# DAC900E.net
KiCad netlist of a schematic drawn in EAGLE
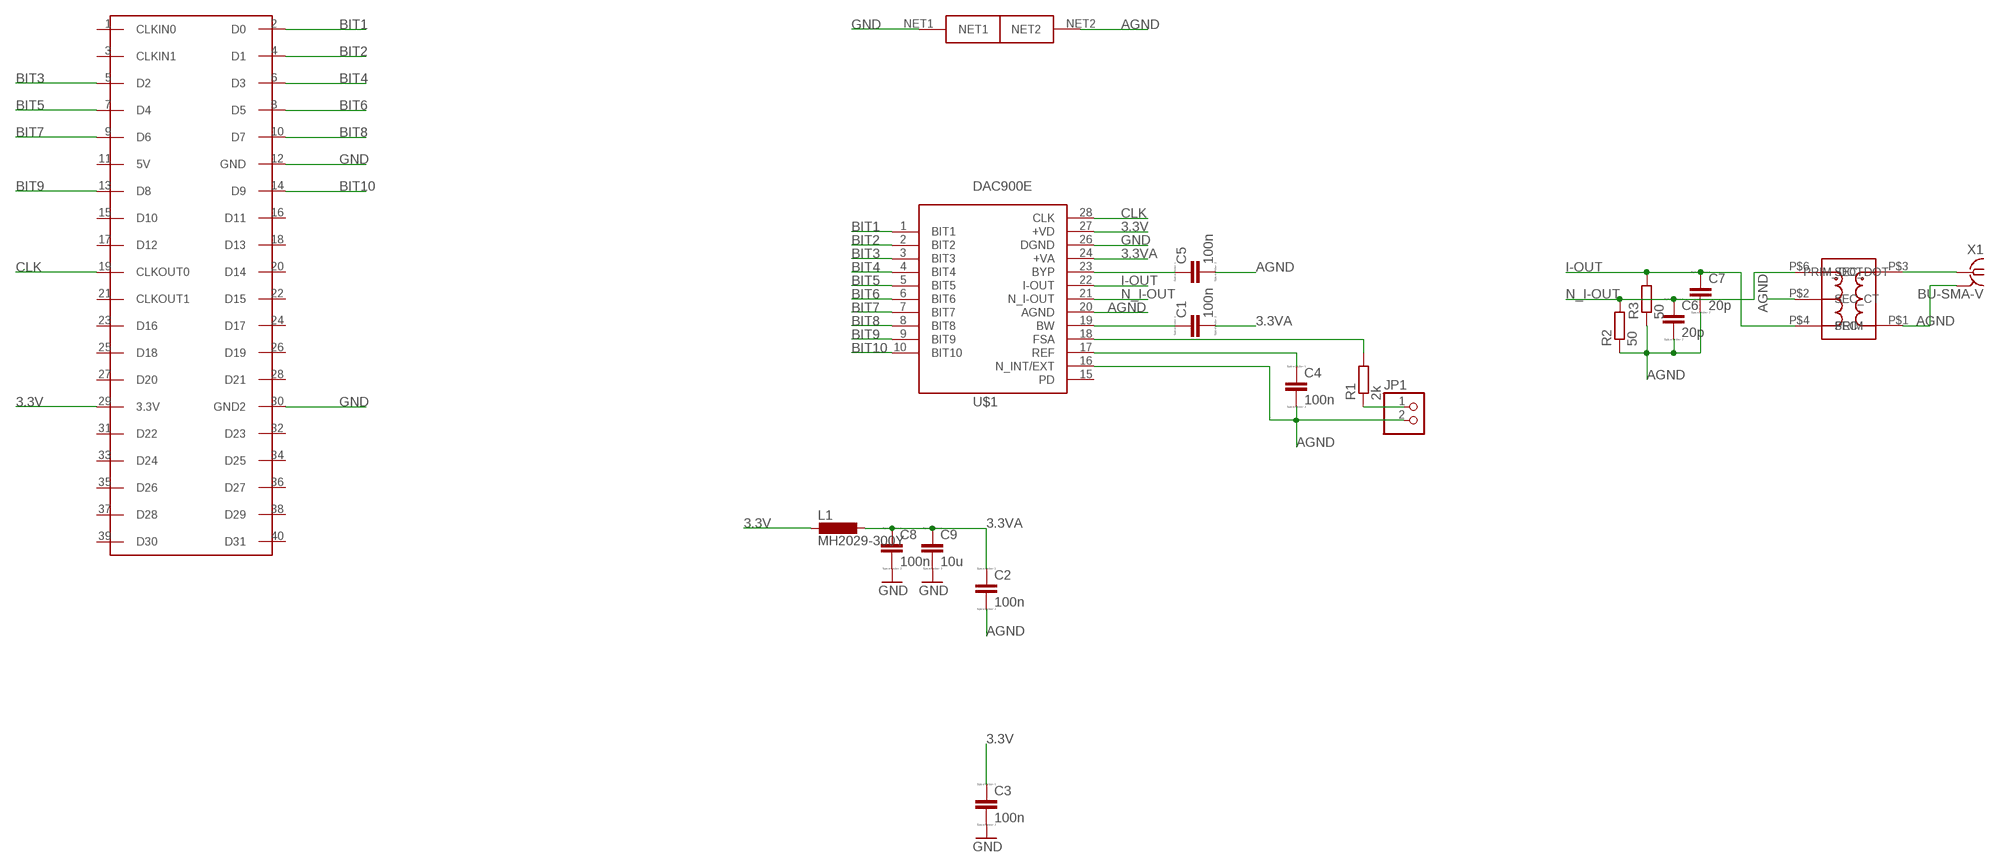
[diagram p0: schematic, sheet 1]

(export (version "E")
  (design (tool "Eeschema 10.0.6"))
  (components
    (comp (ref "C1")
      (value "100n")
      (footprint "eagle-import:C0805")
      (libsource (lib "eagle-import") (part "C_SMD"))
    )
    (comp (ref "C2")
      (value "100n")
      (footprint "eagle-import:C0805")
      (libsource (lib "eagle-import") (part "C_SMD"))
    )
    (comp (ref "C3")
      (value "100n")
      (footprint "eagle-import:C0805")
      (libsource (lib "eagle-import") (part "C_SMD"))
    )
    (comp (ref "C4")
      (value "100n")
      (footprint "eagle-import:C0805")
      (libsource (lib "eagle-import") (part "C_SMD"))
    )
    (comp (ref "C5")
      (value "100n")
      (footprint "eagle-import:C0805")
      (libsource (lib "eagle-import") (part "C_SMD"))
    )
    (comp (ref "C6")
      (value "20p")
      (footprint "eagle-import:C0805")
      (libsource (lib "eagle-import") (part "C_SMD"))
    )
    (comp (ref "C7")
      (value "20p")
      (footprint "eagle-import:C0805")
      (libsource (lib "eagle-import") (part "C_SMD"))
    )
    (comp (ref "C8")
      (value "100n")
      (footprint "eagle-import:C0805")
      (libsource (lib "eagle-import") (part "C_SMD"))
    )
    (comp (ref "C9")
      (value "10u")
      (footprint "eagle-import:C0805")
      (libsource (lib "eagle-import") (part "C_SMD"))
    )
    (comp (ref "JP1")
      (value "PINHD-1X2")
      (footprint "eagle-import:1X02")
      (libsource (lib "eagle-import") (part "PINHD-1X2"))
    )
    (comp (ref "L1")
      (value "MH2029-300Y")
      (footprint "eagle-import:R0805")
      (libsource (lib "eagle-import") (part "L_0805"))
    )
    (comp (ref "R1")
      (value "2k")
      (footprint "eagle-import:R0805")
      (libsource (lib "eagle-import") (part "R-EU_R0805"))
    )
    (comp (ref "R2")
      (value "50")
      (footprint "eagle-import:R0805")
      (libsource (lib "eagle-import") (part "R-EU_R0805"))
    )
    (comp (ref "R3")
      (value "50")
      (footprint "eagle-import:R0805")
      (libsource (lib "eagle-import") (part "R-EU_R0805"))
    )
    (comp (ref "U$1")
      (value "DAC900E")
      (footprint "eagle-import:TSSOP28")
      (libsource (lib "eagle-import") (part "DAC900E"))
    )
    (comp (ref "U$2")
      (value "NET_TIE")
      (footprint "eagle-import:NET-TIE")
      (libsource (lib "eagle-import") (part "NET_TIE"))
    )
    (comp (ref "U$3")
      (value "FPGA_GPIO_DE0")
      (footprint "eagle-import:2X20")
      (libsource (lib "eagle-import") (part "FPGA_GPIO_DE0"))
    )
    (comp (ref "U$4")
      (value "ADT1-1WT")
      (footprint "eagle-import:CD542")
      (libsource (lib "eagle-import") (part "ADT1-1WT"))
    )
    (comp (ref "X1")
      (value "BU-SMA-V")
      (footprint "eagle-import:BU-SMA-V")
      (libsource (lib "eagle-import") (part "BU-SMA-V"))
    )
  )
  (nets
    (net (code "1") (name "/3.3V") (class "Default")
      (node (ref "C3") (pin "1") (pinfunction "1_1") (pintype "passive"))
      (node (ref "L1") (pin "2") (pinfunction "2_2") (pintype "passive"))
      (node (ref "U$1") (pin "27") (pinfunction "+VD_27") (pintype "bidirectional"))
      (node (ref "U$3") (pin "29") (pinfunction "3.3V_29") (pintype "bidirectional"))
    )
    (net (code "2") (name "/3.3VA") (class "Default")
      (node (ref "C1") (pin "2") (pinfunction "2_2") (pintype "passive"))
      (node (ref "C2") (pin "1") (pinfunction "1_1") (pintype "passive"))
      (node (ref "C8") (pin "1") (pinfunction "1_1") (pintype "passive"))
      (node (ref "C9") (pin "1") (pinfunction "1_1") (pintype "passive"))
      (node (ref "L1") (pin "1") (pinfunction "1_1") (pintype "passive"))
      (node (ref "U$1") (pin "24") (pinfunction "+VA_24") (pintype "bidirectional"))
    )
    (net (code "3") (name "/AGND") (class "Default")
      (node (ref "C2") (pin "2") (pinfunction "2_2") (pintype "passive"))
      (node (ref "C4") (pin "2") (pinfunction "2_2") (pintype "passive"))
      (node (ref "C5") (pin "2") (pinfunction "2_2") (pintype "passive"))
      (node (ref "C6") (pin "2") (pinfunction "2_2") (pintype "passive"))
      (node (ref "C7") (pin "2") (pinfunction "2_2") (pintype "passive"))
      (node (ref "JP1") (pin "2") (pinfunction "2_2") (pintype "passive"))
      (node (ref "R2") (pin "1") (pinfunction "1_1") (pintype "passive"))
      (node (ref "R3") (pin "1") (pinfunction "1_1") (pintype "passive"))
      (node (ref "U$1") (pin "16") (pinfunction "N_INT/EXT_16") (pintype "bidirectional"))
      (node (ref "U$1") (pin "20") (pinfunction "AGND_20") (pintype "bidirectional"))
      (node (ref "U$2") (pin "NET2") (pinfunction "NET2_NET2") (pintype "bidirectional"))
      (node (ref "U$4") (pin "P$1") (pinfunction "PRIM_P$1") (pintype "bidirectional"))
      (node (ref "U$4") (pin "P$2") (pinfunction "SEC_CT_P$2") (pintype "bidirectional"))
      (node (ref "X1") (pin "2") (pinfunction "2_2") (pintype "passive"))
      (node (ref "X1") (pin "3") (pinfunction "2_3") (pintype "passive"))
      (node (ref "X1") (pin "4") (pinfunction "2_4") (pintype "passive"))
      (node (ref "X1") (pin "5") (pinfunction "2_5") (pintype "passive"))
    )
    (net (code "4") (name "/BIT1") (class "Default")
      (node (ref "U$1") (pin "1") (pinfunction "BIT1_1") (pintype "bidirectional"))
      (node (ref "U$3") (pin "2") (pinfunction "D0_2") (pintype "bidirectional"))
    )
    (net (code "5") (name "/BIT2") (class "Default")
      (node (ref "U$1") (pin "2") (pinfunction "BIT2_2") (pintype "bidirectional"))
      (node (ref "U$3") (pin "4") (pinfunction "D1_4") (pintype "bidirectional"))
    )
    (net (code "6") (name "/BIT3") (class "Default")
      (node (ref "U$1") (pin "3") (pinfunction "BIT3_3") (pintype "bidirectional"))
      (node (ref "U$3") (pin "5") (pinfunction "D2_5") (pintype "bidirectional"))
    )
    (net (code "7") (name "/BIT4") (class "Default")
      (node (ref "U$1") (pin "4") (pinfunction "BIT4_4") (pintype "bidirectional"))
      (node (ref "U$3") (pin "6") (pinfunction "D3_6") (pintype "bidirectional"))
    )
    (net (code "8") (name "/BIT5") (class "Default")
      (node (ref "U$1") (pin "5") (pinfunction "BIT5_5") (pintype "bidirectional"))
      (node (ref "U$3") (pin "7") (pinfunction "D4_7") (pintype "bidirectional"))
    )
    (net (code "9") (name "/BIT6") (class "Default")
      (node (ref "U$1") (pin "6") (pinfunction "BIT6_6") (pintype "bidirectional"))
      (node (ref "U$3") (pin "8") (pinfunction "D5_8") (pintype "bidirectional"))
    )
    (net (code "10") (name "/BIT7") (class "Default")
      (node (ref "U$1") (pin "7") (pinfunction "BIT7_7") (pintype "bidirectional"))
      (node (ref "U$3") (pin "9") (pinfunction "D6_9") (pintype "bidirectional"))
    )
    (net (code "11") (name "/BIT8") (class "Default")
      (node (ref "U$1") (pin "8") (pinfunction "BIT8_8") (pintype "bidirectional"))
      (node (ref "U$3") (pin "10") (pinfunction "D7_10") (pintype "bidirectional"))
    )
    (net (code "12") (name "/BIT9") (class "Default")
      (node (ref "U$1") (pin "9") (pinfunction "BIT9_9") (pintype "bidirectional"))
      (node (ref "U$3") (pin "13") (pinfunction "D8_13") (pintype "bidirectional"))
    )
    (net (code "13") (name "/BIT10") (class "Default")
      (node (ref "U$1") (pin "10") (pinfunction "BIT10_10") (pintype "bidirectional"))
      (node (ref "U$3") (pin "14") (pinfunction "D9_14") (pintype "bidirectional"))
    )
    (net (code "14") (name "/CLK") (class "Default")
      (node (ref "U$1") (pin "28") (pinfunction "CLK_28") (pintype "bidirectional"))
      (node (ref "U$3") (pin "19") (pinfunction "CLKOUT0_19") (pintype "bidirectional"))
    )
    (net (code "15") (name "/I-OUT") (class "Default")
      (node (ref "C7") (pin "1") (pinfunction "1_1") (pintype "passive"))
      (node (ref "R3") (pin "2") (pinfunction "2_2") (pintype "passive"))
      (node (ref "U$1") (pin "22") (pinfunction "I-OUT_22") (pintype "bidirectional"))
      (node (ref "U$4") (pin "P$4") (pinfunction "SEC_P$4") (pintype "bidirectional"))
    )
    (net (code "16") (name "/N_I-OUT") (class "Default")
      (node (ref "C6") (pin "1") (pinfunction "1_1") (pintype "passive"))
      (node (ref "R2") (pin "2") (pinfunction "2_2") (pintype "passive"))
      (node (ref "U$1") (pin "21") (pinfunction "N_I-OUT_21") (pintype "bidirectional"))
      (node (ref "U$4") (pin "P$6") (pinfunction "SEC_DOT_P$6") (pintype "bidirectional"))
    )
    (net (code "17") (name "GND") (class "Default")
      (node (ref "C3") (pin "2") (pinfunction "2_2") (pintype "passive"))
      (node (ref "C8") (pin "2") (pinfunction "2_2") (pintype "passive"))
      (node (ref "C9") (pin "2") (pinfunction "2_2") (pintype "passive"))
      (node (ref "U$1") (pin "26") (pinfunction "DGND_26") (pintype "bidirectional"))
      (node (ref "U$2") (pin "NET1") (pinfunction "NET1_NET1") (pintype "bidirectional"))
      (node (ref "U$3") (pin "12") (pinfunction "GND_12") (pintype "bidirectional"))
      (node (ref "U$3") (pin "30") (pinfunction "GND2_30") (pintype "bidirectional"))
    )
    (net (code "18") (name "Net-(JP1-Pad1)") (class "Default")
      (node (ref "JP1") (pin "1") (pinfunction "1_1") (pintype "passive"))
      (node (ref "R1") (pin "1") (pinfunction "1_1") (pintype "passive"))
    )
    (net (code "19") (name "Net-(U$1-BW)") (class "Default")
      (node (ref "C1") (pin "1") (pinfunction "1_1") (pintype "passive"))
      (node (ref "U$1") (pin "19") (pinfunction "BW_19") (pintype "bidirectional"))
    )
    (net (code "20") (name "Net-(U$1-BYP)") (class "Default")
      (node (ref "C5") (pin "1") (pinfunction "1_1") (pintype "passive"))
      (node (ref "U$1") (pin "23") (pinfunction "BYP_23") (pintype "bidirectional"))
    )
    (net (code "21") (name "Net-(U$1-FSA)") (class "Default")
      (node (ref "R1") (pin "2") (pinfunction "2_2") (pintype "passive"))
      (node (ref "U$1") (pin "18") (pinfunction "FSA_18") (pintype "bidirectional"))
    )
    (net (code "22") (name "Net-(U$1-REF)") (class "Default")
      (node (ref "C4") (pin "1") (pinfunction "1_1") (pintype "passive"))
      (node (ref "U$1") (pin "17") (pinfunction "REF_17") (pintype "bidirectional"))
    )
    (net (code "23") (name "Net-(U$4-PRIM_DOT)") (class "Default")
      (node (ref "U$4") (pin "P$3") (pinfunction "PRIM_DOT_P$3") (pintype "bidirectional"))
      (node (ref "X1") (pin "1") (pinfunction "1_1") (pintype "passive"))
    )
    (net (code "24") (name "unconnected-(U$1-PD-Pad15)") (class "Default")
      (node (ref "U$1") (pin "15") (pinfunction "PD_15") (pintype "bidirectional"))
    )
    (net (code "25") (name "unconnected-(U$3-5V-Pad11)") (class "Default")
      (node (ref "U$3") (pin "11") (pinfunction "5V_11") (pintype "bidirectional"))
    )
    (net (code "26") (name "unconnected-(U$3-CLKIN0-Pad1)") (class "Default")
      (node (ref "U$3") (pin "1") (pinfunction "CLKIN0_1") (pintype "bidirectional"))
    )
    (net (code "27") (name "unconnected-(U$3-CLKIN1-Pad3)") (class "Default")
      (node (ref "U$3") (pin "3") (pinfunction "CLKIN1_3") (pintype "bidirectional"))
    )
    (net (code "28") (name "unconnected-(U$3-CLKOUT1-Pad21)") (class "Default")
      (node (ref "U$3") (pin "21") (pinfunction "CLKOUT1_21") (pintype "bidirectional"))
    )
    (net (code "29") (name "unconnected-(U$3-D10-Pad15)") (class "Default")
      (node (ref "U$3") (pin "15") (pinfunction "D10_15") (pintype "bidirectional"))
    )
    (net (code "30") (name "unconnected-(U$3-D11-Pad16)") (class "Default")
      (node (ref "U$3") (pin "16") (pinfunction "D11_16") (pintype "bidirectional"))
    )
    (net (code "31") (name "unconnected-(U$3-D12-Pad17)") (class "Default")
      (node (ref "U$3") (pin "17") (pinfunction "D12_17") (pintype "bidirectional"))
    )
    (net (code "32") (name "unconnected-(U$3-D13-Pad18)") (class "Default")
      (node (ref "U$3") (pin "18") (pinfunction "D13_18") (pintype "bidirectional"))
    )
    (net (code "33") (name "unconnected-(U$3-D14-Pad20)") (class "Default")
      (node (ref "U$3") (pin "20") (pinfunction "D14_20") (pintype "bidirectional"))
    )
    (net (code "34") (name "unconnected-(U$3-D15-Pad22)") (class "Default")
      (node (ref "U$3") (pin "22") (pinfunction "D15_22") (pintype "bidirectional"))
    )
    (net (code "35") (name "unconnected-(U$3-D16-Pad23)") (class "Default")
      (node (ref "U$3") (pin "23") (pinfunction "D16_23") (pintype "bidirectional"))
    )
    (net (code "36") (name "unconnected-(U$3-D17-Pad24)") (class "Default")
      (node (ref "U$3") (pin "24") (pinfunction "D17_24") (pintype "bidirectional"))
    )
    (net (code "37") (name "unconnected-(U$3-D18-Pad25)") (class "Default")
      (node (ref "U$3") (pin "25") (pinfunction "D18_25") (pintype "bidirectional"))
    )
    (net (code "38") (name "unconnected-(U$3-D19-Pad26)") (class "Default")
      (node (ref "U$3") (pin "26") (pinfunction "D19_26") (pintype "bidirectional"))
    )
    (net (code "39") (name "unconnected-(U$3-D20-Pad27)") (class "Default")
      (node (ref "U$3") (pin "27") (pinfunction "D20_27") (pintype "bidirectional"))
    )
    (net (code "40") (name "unconnected-(U$3-D21-Pad28)") (class "Default")
      (node (ref "U$3") (pin "28") (pinfunction "D21_28") (pintype "bidirectional"))
    )
    (net (code "41") (name "unconnected-(U$3-D22-Pad31)") (class "Default")
      (node (ref "U$3") (pin "31") (pinfunction "D22_31") (pintype "bidirectional"))
    )
    (net (code "42") (name "unconnected-(U$3-D23-Pad32)") (class "Default")
      (node (ref "U$3") (pin "32") (pinfunction "D23_32") (pintype "bidirectional"))
    )
    (net (code "43") (name "unconnected-(U$3-D24-Pad33)") (class "Default")
      (node (ref "U$3") (pin "33") (pinfunction "D24_33") (pintype "bidirectional"))
    )
    (net (code "44") (name "unconnected-(U$3-D25-Pad34)") (class "Default")
      (node (ref "U$3") (pin "34") (pinfunction "D25_34") (pintype "bidirectional"))
    )
    (net (code "45") (name "unconnected-(U$3-D26-Pad35)") (class "Default")
      (node (ref "U$3") (pin "35") (pinfunction "D26_35") (pintype "bidirectional"))
    )
    (net (code "46") (name "unconnected-(U$3-D27-Pad36)") (class "Default")
      (node (ref "U$3") (pin "36") (pinfunction "D27_36") (pintype "bidirectional"))
    )
    (net (code "47") (name "unconnected-(U$3-D28-Pad37)") (class "Default")
      (node (ref "U$3") (pin "37") (pinfunction "D28_37") (pintype "bidirectional"))
    )
    (net (code "48") (name "unconnected-(U$3-D29-Pad38)") (class "Default")
      (node (ref "U$3") (pin "38") (pinfunction "D29_38") (pintype "bidirectional"))
    )
    (net (code "49") (name "unconnected-(U$3-D30-Pad39)") (class "Default")
      (node (ref "U$3") (pin "39") (pinfunction "D30_39") (pintype "bidirectional"))
    )
    (net (code "50") (name "unconnected-(U$3-D31-Pad40)") (class "Default")
      (node (ref "U$3") (pin "40") (pinfunction "D31_40") (pintype "bidirectional"))
    )
  )
)
